# Oscillators.net
KiCad netlist of a schematic drawn in Altium Designer
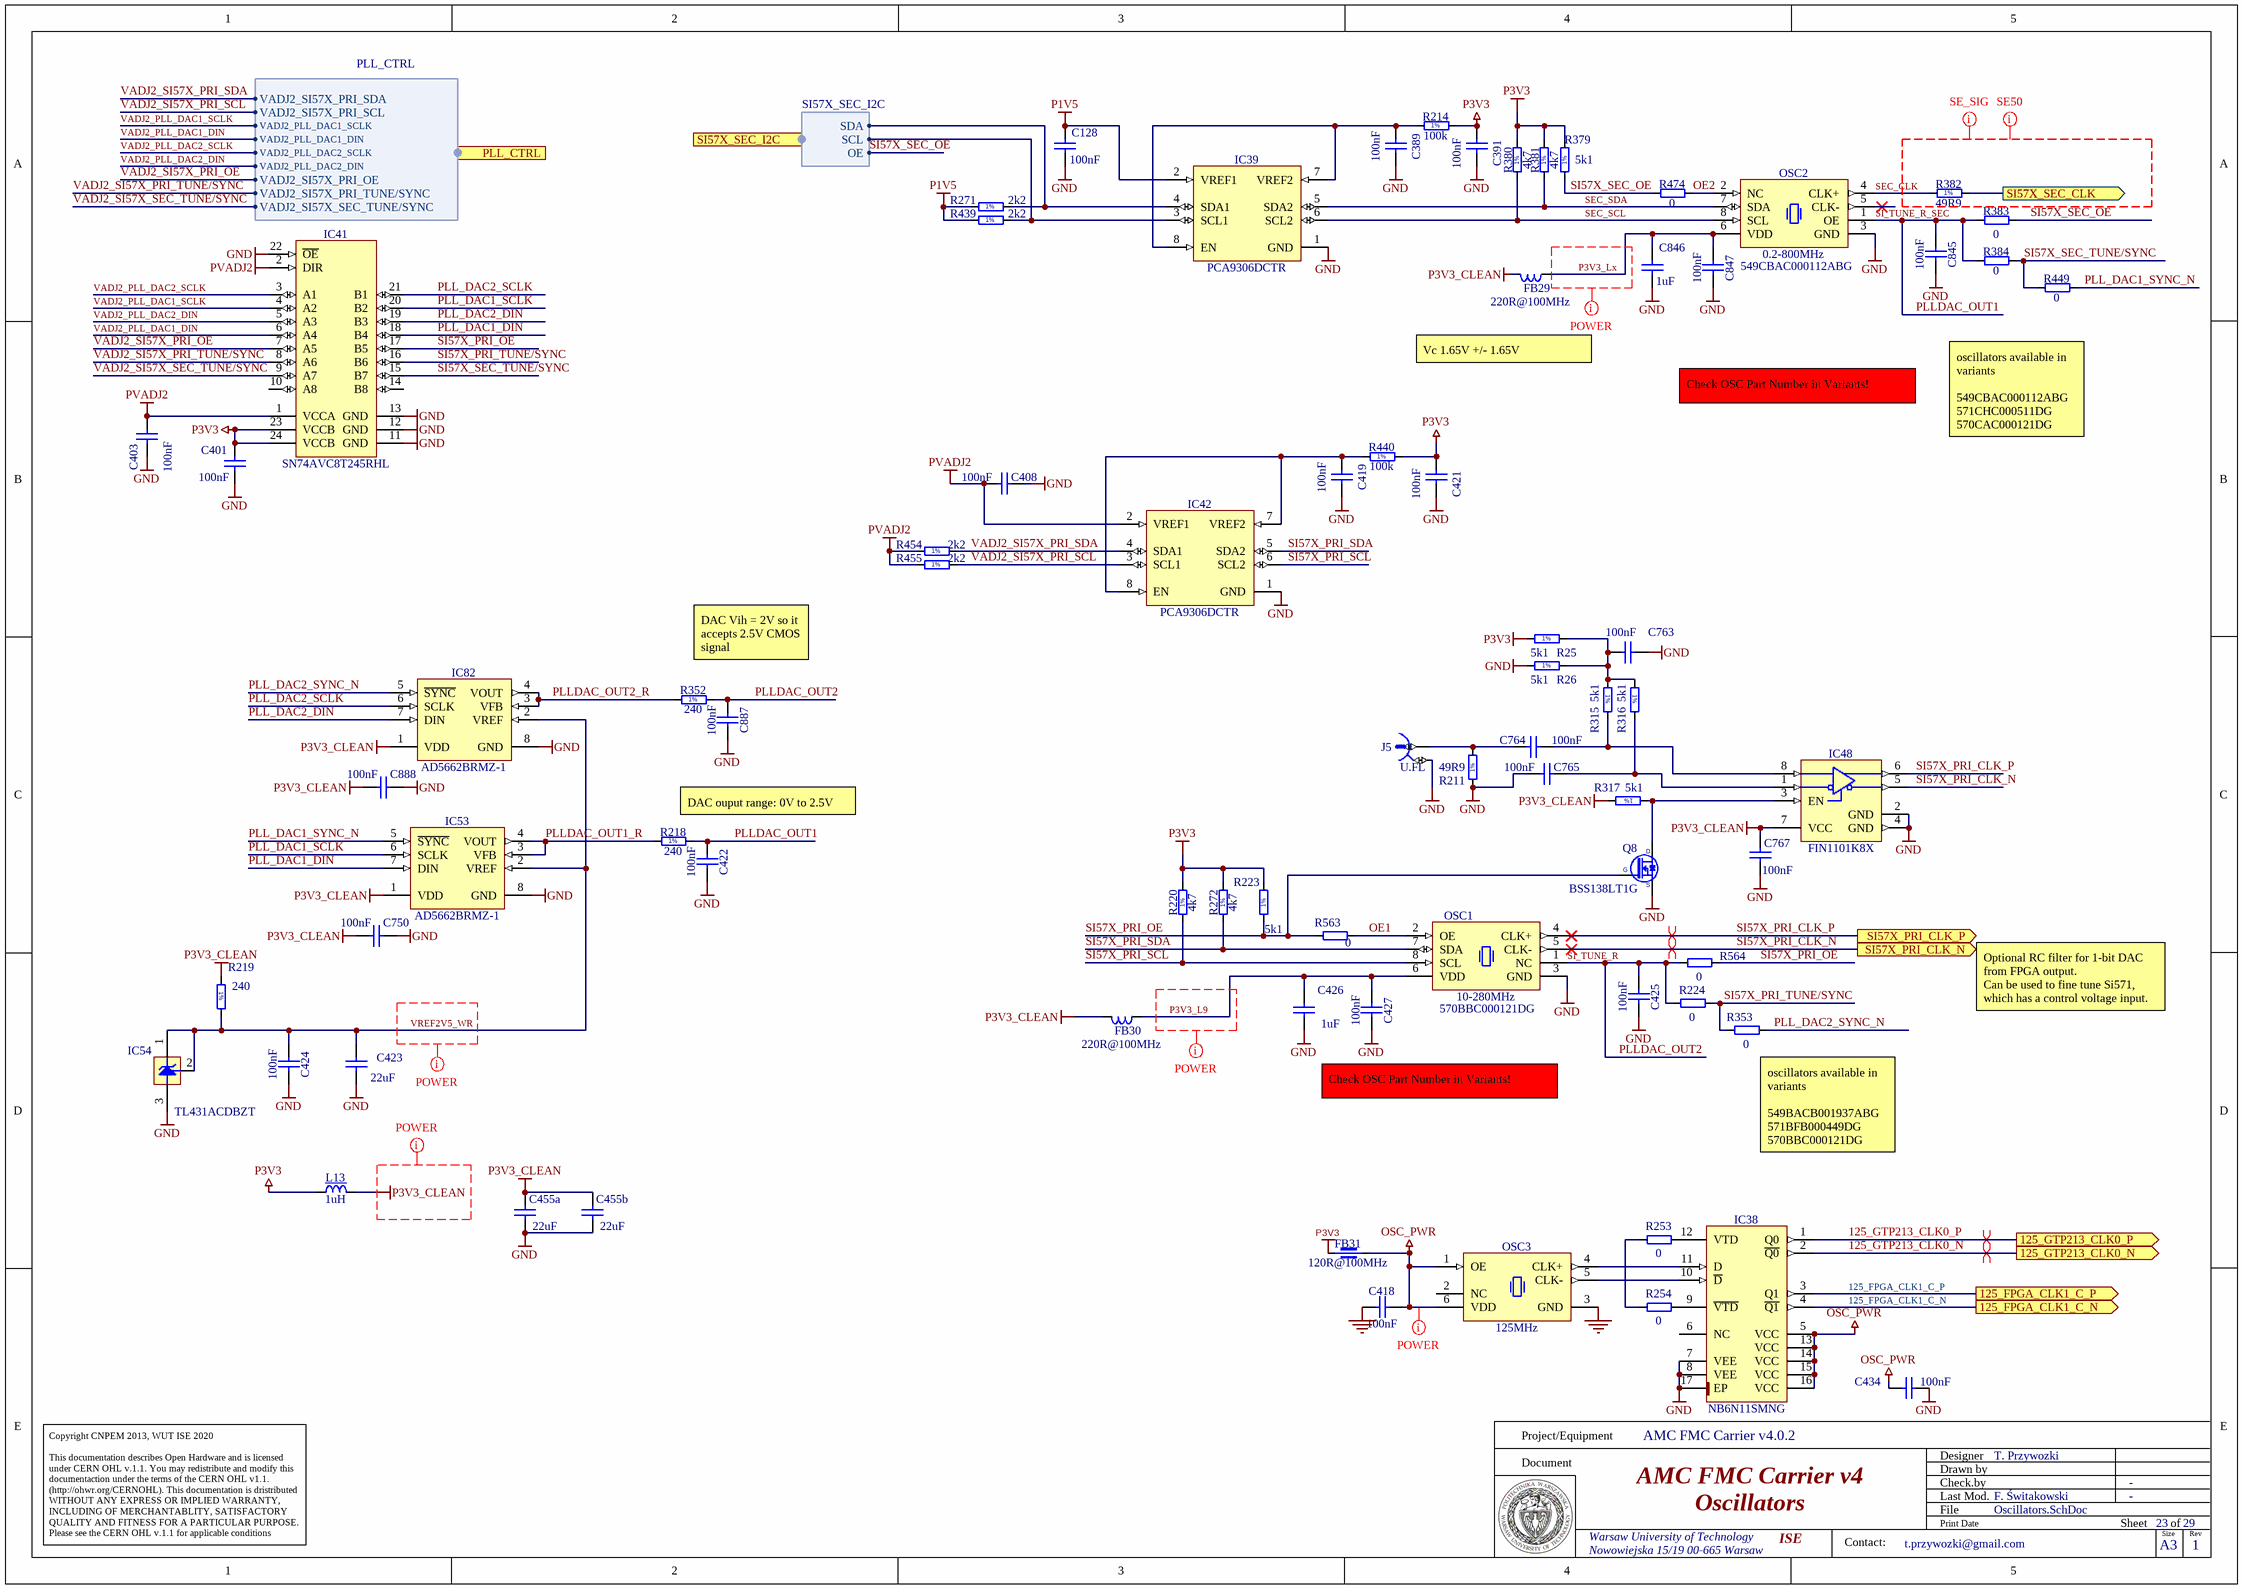
[diagram p0: Oscillators.SchDoc]

(export (version "E")
  (design (tool "Eeschema 10.0.6"))
  (components
    (comp (ref "C128")
      (value "100nF")
      (footprint "CAPC0603X33N")
      (description "Non-polarised capacitor")
      (fields
        (field (name "PART NUMBER") "CC0201_100NF_6.3V_10%_X5R")
        (field (name "VOLTAGE") "6.3V")
        (field (name "AUTHOR") "CERN DEM JLC")
      )
      (libsource (lib "Capacitors") (part "Capacitor - non polarized"))
    )
    (comp (ref "C389")
      (value "100nF")
      (footprint "CAPC0603X33N")
      (description "Non-polarised capacitor")
      (fields
        (field (name "PART NUMBER") "CC0201_100NF_6.3V_10%_X5R")
        (field (name "VOLTAGE") "6.3V")
        (field (name "AUTHOR") "CERN DEM JLC")
      )
      (libsource (lib "Capacitors") (part "Capacitor - non polarized"))
    )
    (comp (ref "C391")
      (value "100nF")
      (footprint "CAPC0603X33N")
      (description "Non-polarised capacitor")
      (fields
        (field (name "PART NUMBER") "CC0201_100NF_6.3V_10%_X5R")
        (field (name "VOLTAGE") "6.3V")
        (field (name "AUTHOR") "CERN DEM JLC")
      )
      (libsource (lib "Capacitors") (part "Capacitor - non polarized"))
    )
    (comp (ref "C401")
      (value "100nF")
      (footprint "CAPC0603X33N")
      (description "Non-polarised capacitor")
      (fields
        (field (name "PART NUMBER") "CC0201_100NF_6.3V_10%_X5R")
        (field (name "VOLTAGE") "6.3V")
        (field (name "AUTHOR") "CERN DEM JLC")
      )
      (libsource (lib "Capacitors") (part "Capacitor - non polarized"))
    )
    (comp (ref "C403")
      (value "100nF")
      (footprint "CAPC0603X33N")
      (description "Non-polarised capacitor")
      (fields
        (field (name "PART NUMBER") "CC0201_100NF_6.3V_10%_X5R")
        (field (name "VOLTAGE") "6.3V")
        (field (name "AUTHOR") "CERN DEM JLC")
      )
      (libsource (lib "Capacitors") (part "Capacitor - non polarized"))
    )
    (comp (ref "C408")
      (value "100nF")
      (footprint "CAPC0603X33N")
      (description "Non-polarised capacitor")
      (fields
        (field (name "PART NUMBER") "CC0201_100NF_6.3V_10%_X5R")
        (field (name "VOLTAGE") "6.3V")
        (field (name "AUTHOR") "CERN DEM JLC")
      )
      (libsource (lib "Capacitors") (part "Capacitor - non polarized"))
    )
    (comp (ref "C418")
      (value "100nF")
      (footprint "CAPC0603X33N")
      (description "Non-polarised capacitor")
      (fields
        (field (name "MANUFACTURER PART NUMBER") "CC0201_100NF_6.3V_10%_X5R")
        (field (name "MANUFACTURER") "GENERIC")
        (field (name "AUTHOR") "CERN DEM JLC")
      )
      (libsource (lib "Capacitors") (part "Capacitor - non polarized"))
    )
    (comp (ref "C419")
      (value "100nF")
      (footprint "CAPC0603X33N")
      (description "Non-polarised capacitor")
      (fields
        (field (name "PART NUMBER") "CC0201_100NF_6.3V_10%_X5R")
        (field (name "VOLTAGE") "6.3V")
        (field (name "AUTHOR") "CERN DEM JLC")
      )
      (libsource (lib "Capacitors") (part "Capacitor - non polarized"))
    )
    (comp (ref "C421")
      (value "100nF")
      (footprint "CAPC0603X33N")
      (description "Non-polarised capacitor")
      (fields
        (field (name "PART NUMBER") "CC0201_100NF_6.3V_10%_X5R")
        (field (name "VOLTAGE") "6.3V")
        (field (name "AUTHOR") "CERN DEM JLC")
      )
      (libsource (lib "Capacitors") (part "Capacitor - non polarized"))
    )
    (comp (ref "C422")
      (value "100nF")
      (footprint "CAPC0603X33N")
      (description "Non-polarised capacitor")
      (fields
        (field (name "PART NUMBER") "CC0201_100NF_6.3V_10%_X5R")
        (field (name "VOLTAGE") "6.3V")
        (field (name "AUTHOR") "CERN DEM JLC")
      )
      (libsource (lib "Capacitors") (part "Capacitor - non polarized"))
    )
    (comp (ref "C423")
      (value "22uF")
      (footprint "CAPC3216X180N")
      (description "Non-polarised capacitor")
      (fields
        (field (name "PART NUMBER") "CC1206_22UF_10V_10%_X7R")
        (field (name "VOLTAGE") "10V")
        (field (name "AUTHOR") "CERN DEM JLC")
      )
      (libsource (lib "Capacitors") (part "Capacitor - non polarized"))
    )
    (comp (ref "C424")
      (value "100nF")
      (footprint "CAPC0603X33N")
      (description "Non-polarised capacitor")
      (fields
        (field (name "PART NUMBER") "CC0201_100NF_6.3V_10%_X5R")
        (field (name "VOLTAGE") "6.3V")
        (field (name "AUTHOR") "CERN DEM JLC")
      )
      (libsource (lib "Capacitors") (part "Capacitor - non polarized"))
    )
    (comp (ref "C425")
      (value "100nF")
      (footprint "CAPC0603X33N")
      (description "Non-polarised capacitor")
      (fields
        (field (name "PART NUMBER") "CC0201_100NF_6.3V_10%_X5R")
        (field (name "VOLTAGE") "6.3V")
        (field (name "AUTHOR") "CERN DEM JLC")
      )
      (libsource (lib "Capacitors") (part "Capacitor - non polarized"))
    )
    (comp (ref "C426")
      (value "1uF")
      (footprint "CAPC1608X87N")
      (description "Non-polarised capacitor")
      (fields
        (field (name "PART NUMBER") "CC0603_1UF_16V_10%_X7R")
        (field (name "VOLTAGE") "16V")
        (field (name "AUTHOR") "CERN DEM JLC")
      )
      (libsource (lib "Capacitors") (part "Capacitor - non polarized"))
    )
    (comp (ref "C427")
      (value "100nF")
      (footprint "CAPC0603X33N")
      (description "Non-polarised capacitor")
      (fields
        (field (name "PART NUMBER") "CC0201_100NF_6.3V_10%_X5R")
        (field (name "VOLTAGE") "6.3V")
        (field (name "AUTHOR") "CERN DEM JLC")
      )
      (libsource (lib "Capacitors") (part "Capacitor - non polarized"))
    )
    (comp (ref "C434")
      (value "100nF")
      (footprint "CAPC0603X33N")
      (description "Non-polarised capacitor")
      (fields
        (field (name "PART NUMBER") "CC0201_100NF_6.3V_10%_X5R")
        (field (name "VOLTAGE") "6.3V")
        (field (name "AUTHOR") "CERN DEM JLC")
      )
      (libsource (lib "Capacitors") (part "Capacitor - non polarized"))
    )
    (comp (ref "C455a")
      (value "22uF")
      (footprint "CAPC3216X180N")
      (description "Non-polarised capacitor")
      (fields
        (field (name "PART NUMBER") "CC1206_22UF_10V_10%_X7R")
        (field (name "VOLTAGE") "10V")
        (field (name "AUTHOR") "CERN DEM JLC")
      )
      (libsource (lib "Capacitors") (part "Capacitor - non polarized"))
    )
    (comp (ref "C455b")
      (value "22uF")
      (footprint "CAPC3216X180N")
      (description "Non-polarised capacitor")
      (fields
        (field (name "PART NUMBER") "CC1206_22UF_10V_10%_X7R")
        (field (name "VOLTAGE") "10V")
        (field (name "AUTHOR") "CERN DEM JLC")
      )
      (libsource (lib "Capacitors") (part "Capacitor - non polarized"))
    )
    (comp (ref "C750")
      (value "100nF")
      (footprint "CAPC0603X33N")
      (description "Non-polarised capacitor")
      (fields
        (field (name "PART NUMBER") "CC0201_100NF_6.3V_10%_X5R")
        (field (name "VOLTAGE") "6.3V")
        (field (name "AUTHOR") "CERN DEM JLC")
      )
      (libsource (lib "Capacitors") (part "Capacitor - non polarized"))
    )
    (comp (ref "C763")
      (value "100nF")
      (footprint "CAPC0603X33N")
      (description "Non-polarised capacitor")
      (fields
        (field (name "PART NUMBER") "CC0201_100NF_6.3V_10%_X5R")
        (field (name "VOLTAGE") "6.3V")
        (field (name "AUTHOR") "CERN DEM JLC")
      )
      (libsource (lib "Capacitors") (part "Capacitor - non polarized"))
    )
    (comp (ref "C764")
      (value "100nF")
      (footprint "CAPC0603X33N")
      (description "Non-polarised capacitor")
      (fields
        (field (name "PART NUMBER") "CC0201_100NF_6.3V_10%_X5R")
        (field (name "VOLTAGE") "6.3V")
        (field (name "AUTHOR") "CERN DEM JLC")
      )
      (libsource (lib "Capacitors") (part "Capacitor - non polarized"))
    )
    (comp (ref "C765")
      (value "100nF")
      (footprint "CAPC0603X33N")
      (description "Non-polarised capacitor")
      (fields
        (field (name "PART NUMBER") "CC0201_100NF_6.3V_10%_X5R")
        (field (name "VOLTAGE") "6.3V")
        (field (name "AUTHOR") "CERN DEM JLC")
      )
      (libsource (lib "Capacitors") (part "Capacitor - non polarized"))
    )
    (comp (ref "C767")
      (value "100nF")
      (footprint "CAPC0603X33N")
      (description "Non-polarised capacitor")
      (fields
        (field (name "PART NUMBER") "CC0201_100NF_6.3V_10%_X5R")
        (field (name "VOLTAGE") "6.3V")
        (field (name "AUTHOR") "CERN DEM JLC")
      )
      (libsource (lib "Capacitors") (part "Capacitor - non polarized"))
    )
    (comp (ref "C845")
      (value "100nF")
      (footprint "CAPC0603X33N")
      (description "Non-polarised capacitor")
      (fields
        (field (name "PART NUMBER") "CC0201_100NF_6.3V_10%_X5R")
        (field (name "VOLTAGE") "6.3V")
        (field (name "AUTHOR") "CERN DEM JLC")
      )
      (libsource (lib "Capacitors") (part "Capacitor - non polarized"))
    )
    (comp (ref "C846")
      (value "1uF")
      (footprint "CAPC1608X87N")
      (description "Non-polarised capacitor")
      (fields
        (field (name "PART NUMBER") "CC0603_1UF_16V_10%_X7R")
        (field (name "VOLTAGE") "16V")
        (field (name "AUTHOR") "CERN DEM JLC")
      )
      (libsource (lib "Capacitors") (part "Capacitor - non polarized"))
    )
    (comp (ref "C847")
      (value "100nF")
      (footprint "CAPC0603X33N")
      (description "Non-polarised capacitor")
      (fields
        (field (name "PART NUMBER") "CC0201_100NF_6.3V_10%_X5R")
        (field (name "VOLTAGE") "6.3V")
        (field (name "AUTHOR") "CERN DEM JLC")
      )
      (libsource (lib "Capacitors") (part "Capacitor - non polarized"))
    )
    (comp (ref "C887")
      (value "100nF")
      (footprint "CAPC0603X33N")
      (description "Non-polarised capacitor")
      (fields
        (field (name "PART NUMBER") "CC0201_100NF_6.3V_10%_X5R")
        (field (name "VOLTAGE") "6.3V")
        (field (name "AUTHOR") "CERN DEM JLC")
      )
      (libsource (lib "Capacitors") (part "Capacitor - non polarized"))
    )
    (comp (ref "C888")
      (value "100nF")
      (footprint "CAPC0603X33N")
      (description "Non-polarised capacitor")
      (fields
        (field (name "PART NUMBER") "CC0201_100NF_6.3V_10%_X5R")
        (field (name "VOLTAGE") "6.3V")
        (field (name "AUTHOR") "CERN DEM JLC")
      )
      (libsource (lib "Capacitors") (part "Capacitor - non polarized"))
    )
    (comp (ref "FB29")
      (value "220R@100MHz")
      (footprint "INDC2012X105N")
      (description "Inductor")
      (fields
        (field (name "PART NUMBER") "IND0805_MURATA_BLM21PG221SN1D")
        (field (name "POWER") "2A")
        (field (name "AUTHOR") "CERN DEM JLC")
      )
      (libsource (lib "Inductors & Transformers") (part "Inductor"))
    )
    (comp (ref "FB30")
      (value "220R@100MHz")
      (footprint "INDC2012X105N")
      (description "Inductor")
      (fields
        (field (name "PART NUMBER") "IND0805_MURATA_BLM21PG221SN1D")
        (field (name "POWER") "2A")
        (field (name "AUTHOR") "CERN DEM JLC")
      )
      (libsource (lib "Inductors & Transformers") (part "Inductor"))
    )
    (comp (ref "FB31")
      (value "120R@100MHz")
      (footprint "INDC1005X55N")
      (fields
        (field (name "MANUFACTURER PART NUMBER") "BLM15PX121SN1D")
        (field (name "MANUFACTURER") "MURATA")
        (field (name "PART NUMBER") "IND0402_MURATA_BLM15PX121SN1D")
        (field (name "AUTHOR") "CERN DEM JMW")
      )
      (libsource (lib "Inductors & Transformers") (part "Ferrite Bead"))
    )
    (comp (ref "IC38")
      (value "NB6N11SMNG")
      (footprint "QFN50P300X300X100-17N-S185")
      (description "3.3V 1:2 AnyLevel Input to LVDS Fanout Buffer / Translator")
      (fields (field (name "MANUFACTURER") "ON SEMICONDUCTOR") (field (name "AUTHOR") "CERN DEM JLC"))
      (libsource (lib "ICs And Semiconductors") (part "NB6N11SMN"))
    )
    (comp (ref "IC39")
      (value "PCA9306DCTR")
      (footprint "SOP65P400X130-8N")
      (description "Dual Bidirectional I2C Bus And SMBus Voltage-Level Translator")
      (fields (field (name "MANUFACTURER") "TEXAS INSTRUMENTS") (field (name "AUTHOR") "CERN DEM JLC"))
      (libsource (lib "ICs And Semiconductors") (part "PCA9306D"))
    )
    (comp (ref "IC41")
      (value "SN74AVC8T245RHL")
      (footprint "TEXAS_RHL (S-PVQFN-N24)")
      (description "8-Bit Dual-Supply Bus Transceiver With Configurable Voltage Translation and 3-State Outputs")
      (fields (field (name "MANUFACTURER") "TEXAS INSTRUMENTS") (field (name "AUTHOR") "CERN DEM MR"))
      (libsource (lib "ICs And Semiconductors") (part "748T245"))
    )
    (comp (ref "IC42")
      (value "PCA9306DCTR")
      (footprint "SOP65P400X130-8N")
      (description "Dual Bidirectional I2C Bus And SMBus Voltage-Level Translator")
      (fields (field (name "MANUFACTURER") "TEXAS INSTRUMENTS") (field (name "AUTHOR") "CERN DEM JLC"))
      (libsource (lib "ICs And Semiconductors") (part "PCA9306D"))
    )
    (comp (ref "IC48")
      (value "FIN1101K8X")
      (footprint "SOP50P310X90-8N")
      (description "LVDS Single Port High Speed Repeater")
      (fields (field (name "MANUFACTURER") "FAIRCHILD SEMICONDUCTOR") (field (name "AUTHOR") "CERN DEM JLC"))
      (libsource (lib "ICs And Semiconductors") (part "FIN1101K8X"))
    )
    (comp (ref "IC53")
      (value "AD5662BRMZ-1")
      (footprint "SOP65P490X110-8N")
      (description "2.7V to 5.5V, 250uA, Rail-to-Rail Output 16-Bit nanoDAC")
      (fields (field (name "MANUFACTURER") "ANALOG DEVICES") (field (name "AUTHOR") "CERN DEM JLC"))
      (libsource (lib "ICs And Semiconductors") (part "AD5662"))
    )
    (comp (ref "IC54")
      (value "TL431ACDBZT")
      (footprint "SOT95P237X112-3N")
      (description "Precision Reference 1=Cathode 2=Adj 3=Anode")
      (fields (field (name "MANUFACTURER") "TEXAS INSTRUMENTS") (field (name "AUTHOR") "CERN DEM JLC"))
      (libsource (lib "ICs And Semiconductors") (part "VREF 1C-2ADJ-3A"))
    )
    (comp (ref "IC82")
      (value "AD5662BRMZ-1")
      (footprint "SOP65P490X110-8N")
      (description "2.7V to 5.5V, 250uA, Rail-to-Rail Output 16-Bit nanoDAC")
      (fields (field (name "MANUFACTURER") "ANALOG DEVICES") (field (name "AUTHOR") "CERN DEM JLC"))
      (libsource (lib "ICs And Semiconductors") (part "AD5662"))
    )
    (comp (ref "J5")
      (value "U.FL")
      (footprint "HIROSE_U.FL-R-SMT-1(10)")
      (fields
        (field (name "PART NUMBER") "HIROSE_U.FL-R-SMT-1(10)")
        (field (name "MANUFACTURER") "HIROSE (HRS)")
        (field (name "MANUFACTURER PART NUMBER") "U.FL-R-SMT-1(10)")
        (field (name "AUTHOR") "CERN DEM JLC")
      )
      (libsource (lib "Connectors") (part "Coax_1Male_1Shield"))
    )
    (comp (ref "L13")
      (value "1uH")
      (footprint "IND_PANASONIC_ELLVGG")
      (description "Inductor With Core")
      (fields
        (field (name "PART NUMBER") "IND_1UH_30%_PANASONIC_ELLVGG1R0N")
        (field (name "POWER") "1.8A")
        (field (name "AUTHOR") "CERN DEM JLC")
      )
      (libsource (lib "Inductors & Transformers") (part "Inductor With Magnetic core"))
    )
    (comp (ref "OSC1")
      (value "10-280MHz")
      (footprint "OSC_SILICON-LAB_SI570")
      (description "Any-Rate I2C Programmable XO Oscillator Si570 Serie")
      (fields
        (field (name "PART NUMBER") "OSC_10-280MHZ_SILICON-LAB_Si570BBC000121DG")
        (field (name "MANUFACTURER") "SILICON LABS")
        (field (name "MANUFACTURER PART NUMBER") "570BBC000121DG")
        (field (name "AUTHOR") "CERN DEM JLC")
      )
      (libsource (lib "ICs And Semiconductors") (part "Oscillator SILICON-LAB_Si570"))
    )
    (comp (ref "OSC2")
      (value "0.2-800MHz")
      (footprint "OSC_SILICON-LAB_SI549-A")
      (description "Ultra Low Jitter I2C Programmable Crystal Oscillator (XO), Si549 Series")
      (fields
        (field (name "PART NUMBER") "OSC_0.2-800MHZ_SILICON-LAB_549BACB001937ABG")
        (field (name "MANUFACTURER") "SILICON LABS")
        (field (name "MANUFACTURER PART NUMBER") "549CBAC000112ABG")
        (field (name "AUTHOR") "CERN DEM JMW")
      )
      (libsource (lib "ICs And Semiconductors") (part "Oscillator SILICON-LAB_Si549-CD"))
    )
    (comp (ref "OSC3")
      (value "125MHz")
      (footprint "OSC_SILICON-LAB_SI511-6N(3.2X5)")
      (description "Crystal Oscillator 6 pins, Si511 (LVDS/LVPECL/HCSL/Dual CMOS)")
      (fields
        (field (name "PART NUMBER") "OSC_125MHZ_SILICON-LAB_511BBA125M000BAGR")
        (field (name "MANUFACTURER") "SILICON LABS")
        (field (name "AUTHOR") "CERN DEM JLC")
      )
      (libsource (lib "ICs And Semiconductors") (part "Oscillator SILICON-LAB_Si511-6N"))
    )
    (comp (ref "Q8")
      (value "BSS138LT1G")
      (footprint "SOT95P240X110-3N")
      (description "N-CHANNEL MOSFET WITH DIODE")
      (fields (field (name "MANUFACTURER") "ON SEMICONDUCTOR") (field (name "AUTHOR") "CERN DEM JLC"))
      (libsource (lib "ICs And Semiconductors") (part "N-MOSFET-D 1G 2S 3D"))
    )
    (comp (ref "R25")
      (value "5k1")
      (footprint "RESC1608X55N")
      (description "Resistor - 1%")
      (fields
        (field (name "PART NUMBER") "R0603_5K1_1%_0.1W_100PPM")
        (field (name "POWER") "0.1W")
        (field (name "AUTHOR") "CERN DEM JLC")
      )
      (libsource (lib "Resistors") (part "Resistor - 1%"))
    )
    (comp (ref "R26")
      (value "5k1")
      (footprint "RESC1608X55N")
      (description "Resistor - 1%")
      (fields
        (field (name "PART NUMBER") "R0603_5K1_1%_0.1W_100PPM")
        (field (name "POWER") "0.1W")
        (field (name "AUTHOR") "CERN DEM JLC")
      )
      (libsource (lib "Resistors") (part "Resistor - 1%"))
    )
    (comp (ref "R211")
      (value "49R9")
      (footprint "RESC1005X40N")
      (description "Resistor - 1%")
      (fields
        (field (name "PART NUMBER") "R0402_49R9_1%_0.0625W_100PPM")
        (field (name "POWER") "0.0625W")
        (field (name "AUTHOR") "CERN DEM JLC")
      )
      (libsource (lib "Resistors") (part "Resistor - 1%"))
    )
    (comp (ref "R214")
      (value "100k")
      (footprint "RESC1005X40N")
      (description "Resistor - 1%")
      (fields
        (field (name "PART NUMBER") "R0402_100K_1%_0.0625W_100PPM")
        (field (name "POWER") "0.0625W")
        (field (name "AUTHOR") "CERN DEM JLC")
      )
      (libsource (lib "Resistors") (part "Resistor - 1%"))
    )
    (comp (ref "R218")
      (value "240")
      (footprint "RESC1005X40N")
      (description "Resistor - 1%")
      (fields
        (field (name "PART NUMBER") "R0402_240R_1%_0.0625W_100PPM")
        (field (name "POWER") "0.0625W")
        (field (name "AUTHOR") "CERN DEM JLC")
      )
      (libsource (lib "Resistors") (part "Resistor - 1%"))
    )
    (comp (ref "R219")
      (value "240")
      (footprint "RESC1005X40N")
      (description "Resistor - 1%")
      (fields
        (field (name "PART NUMBER") "R0402_240R_1%_0.0625W_100PPM")
        (field (name "POWER") "0.0625W")
        (field (name "AUTHOR") "CERN DEM JLC")
      )
      (libsource (lib "Resistors") (part "Resistor - 1%"))
    )
    (comp (ref "R220")
      (value "4k7")
      (footprint "RESC1005X40N")
      (description "Resistor - 1%")
      (fields
        (field (name "MANUFACTURER PART NUMBER") "R0402_4K7_1%_0.0625W_100PPM")
        (field (name "MANUFACTURER") "GENERIC")
        (field (name "AUTHOR") "CERN DEM JLC")
      )
      (libsource (lib "Resistors") (part "Resistor - 1%"))
    )
    (comp (ref "R223")
      (value "5k1")
      (footprint "RESC1608X55N")
      (description "Resistor - 1%")
      (fields
        (field (name "PART NUMBER") "R0603_5K1_1%_0.1W_100PPM")
        (field (name "POWER") "0.1W")
        (field (name "AUTHOR") "CERN DEM JLC")
      )
      (libsource (lib "Resistors") (part "Resistor - 1%"))
    )
    (comp (ref "R224")
      (value "0")
      (footprint "RESC1005X40N")
      (description "Resistor")
      (fields
        (field (name "PART NUMBER") "R0402_0R_JUMPER")
        (field (name "MANUFACTURER") "GENERIC")
        (field (name "AUTHOR") "CERN DEM JLC")
      )
      (libsource (lib "Resistors") (part "Resistor"))
    )
    (comp (ref "R253")
      (value "0")
      (footprint "RESC1005X40N")
      (description "Resistor")
      (fields
        (field (name "PART NUMBER") "R0402_0R_JUMPER")
        (field (name "MANUFACTURER") "GENERIC")
        (field (name "AUTHOR") "CERN DEM JLC")
      )
      (libsource (lib "Resistors") (part "Resistor"))
    )
    (comp (ref "R254")
      (value "0")
      (footprint "RESC1005X40N")
      (description "Resistor")
      (fields
        (field (name "PART NUMBER") "R0402_0R_JUMPER")
        (field (name "MANUFACTURER") "GENERIC")
        (field (name "AUTHOR") "CERN DEM JLC")
      )
      (libsource (lib "Resistors") (part "Resistor"))
    )
    (comp (ref "R271")
      (value "2k2")
      (footprint "RESC1005X40N")
      (description "Resistor - 1%")
      (fields
        (field (name "PART NUMBER") "R0402_2K2_1%_0.0625W_100PPM")
        (field (name "POWER") "0.0625W")
        (field (name "AUTHOR") "CERN DEM JLC")
      )
      (libsource (lib "Resistors") (part "Resistor - 1%"))
    )
    (comp (ref "R272")
      (value "4k7")
      (footprint "RESC1005X40N")
      (description "Resistor - 1%")
      (fields
        (field (name "MANUFACTURER PART NUMBER") "R0402_4K7_1%_0.0625W_100PPM")
        (field (name "MANUFACTURER") "GENERIC")
        (field (name "AUTHOR") "CERN DEM JLC")
      )
      (libsource (lib "Resistors") (part "Resistor - 1%"))
    )
    (comp (ref "R315")
      (value "5k1")
      (footprint "RESC1608X55N")
      (description "Resistor - 1%")
      (fields
        (field (name "PART NUMBER") "R0603_5K1_1%_0.1W_100PPM")
        (field (name "POWER") "0.1W")
        (field (name "AUTHOR") "CERN DEM JLC")
      )
      (libsource (lib "Resistors") (part "Resistor - 1%"))
    )
    (comp (ref "R316")
      (value "5k1")
      (footprint "RESC1608X55N")
      (description "Resistor - 1%")
      (fields
        (field (name "PART NUMBER") "R0603_5K1_1%_0.1W_100PPM")
        (field (name "POWER") "0.1W")
        (field (name "AUTHOR") "CERN DEM JLC")
      )
      (libsource (lib "Resistors") (part "Resistor - 1%"))
    )
    (comp (ref "R317")
      (value "5k1")
      (footprint "RESC1608X55N")
      (description "Resistor - 1%")
      (fields
        (field (name "PART NUMBER") "R0603_5K1_1%_0.1W_100PPM")
        (field (name "POWER") "0.1W")
        (field (name "AUTHOR") "CERN DEM JLC")
      )
      (libsource (lib "Resistors") (part "Resistor - 1%"))
    )
    (comp (ref "R352")
      (value "240")
      (footprint "RESC1005X40N")
      (description "Resistor - 1%")
      (fields
        (field (name "PART NUMBER") "R0402_240R_1%_0.0625W_100PPM")
        (field (name "POWER") "0.0625W")
        (field (name "AUTHOR") "CERN DEM JLC")
      )
      (libsource (lib "Resistors") (part "Resistor - 1%"))
    )
    (comp (ref "R353")
      (value "0")
      (footprint "RESC1005X40N")
      (description "Resistor")
      (fields
        (field (name "PART NUMBER") "R0402_0R_JUMPER")
        (field (name "MANUFACTURER") "GENERIC")
        (field (name "AUTHOR") "CERN DEM JLC")
      )
      (libsource (lib "Resistors") (part "Resistor"))
    )
    (comp (ref "R379")
      (value "5k1")
      (footprint "RESC1608X55N")
      (description "Resistor - 1%")
      (fields
        (field (name "PART NUMBER") "R0603_5K1_1%_0.1W_100PPM")
        (field (name "POWER") "0.1W")
        (field (name "AUTHOR") "CERN DEM JLC")
      )
      (libsource (lib "Resistors") (part "Resistor - 1%"))
    )
    (comp (ref "R380")
      (value "4k7")
      (footprint "RESC1005X40N")
      (description "Resistor - 1%")
      (fields
        (field (name "MANUFACTURER PART NUMBER") "R0402_4K7_1%_0.0625W_100PPM")
        (field (name "MANUFACTURER") "GENERIC")
        (field (name "AUTHOR") "CERN DEM JLC")
      )
      (libsource (lib "Resistors") (part "Resistor - 1%"))
    )
    (comp (ref "R381")
      (value "4k7")
      (footprint "RESC1005X40N")
      (description "Resistor - 1%")
      (fields
        (field (name "MANUFACTURER PART NUMBER") "R0402_4K7_1%_0.0625W_100PPM")
        (field (name "MANUFACTURER") "GENERIC")
        (field (name "AUTHOR") "CERN DEM JLC")
      )
      (libsource (lib "Resistors") (part "Resistor - 1%"))
    )
    (comp (ref "R382")
      (value "49R9")
      (footprint "RESC1005X40N")
      (description "Resistor - 1%")
      (fields
        (field (name "PART NUMBER") "R0402_49R9_1%_0.0625W_100PPM")
        (field (name "POWER") "0.0625W")
        (field (name "AUTHOR") "CERN DEM JLC")
      )
      (libsource (lib "Resistors") (part "Resistor - 1%"))
    )
    (comp (ref "R383")
      (value "0")
      (footprint "RESC1005X40N")
      (description "Resistor")
      (fields
        (field (name "PART NUMBER") "R0402_0R_JUMPER")
        (field (name "MANUFACTURER") "GENERIC")
        (field (name "AUTHOR") "CERN DEM JLC")
      )
      (libsource (lib "Resistors") (part "Resistor"))
    )
    (comp (ref "R384")
      (value "0")
      (footprint "RESC1005X40N")
      (description "Resistor")
      (fields
        (field (name "PART NUMBER") "R0402_0R_JUMPER")
        (field (name "MANUFACTURER") "GENERIC")
        (field (name "AUTHOR") "CERN DEM JLC")
      )
      (libsource (lib "Resistors") (part "Resistor"))
    )
    (comp (ref "R439")
      (value "2k2")
      (footprint "RESC1005X40N")
      (description "Resistor - 1%")
      (fields
        (field (name "PART NUMBER") "R0402_2K2_1%_0.0625W_100PPM")
        (field (name "POWER") "0.0625W")
        (field (name "AUTHOR") "CERN DEM JLC")
      )
      (libsource (lib "Resistors") (part "Resistor - 1%"))
    )
    (comp (ref "R440")
      (value "100k")
      (footprint "RESC1005X40N")
      (description "Resistor - 1%")
      (fields
        (field (name "PART NUMBER") "R0402_100K_1%_0.0625W_100PPM")
        (field (name "POWER") "0.0625W")
        (field (name "AUTHOR") "CERN DEM JLC")
      )
      (libsource (lib "Resistors") (part "Resistor - 1%"))
    )
    (comp (ref "R449")
      (value "0")
      (footprint "RESC1005X40N")
      (description "Resistor")
      (fields
        (field (name "PART NUMBER") "R0402_0R_JUMPER")
        (field (name "MANUFACTURER") "GENERIC")
        (field (name "AUTHOR") "CERN DEM JLC")
      )
      (libsource (lib "Resistors") (part "Resistor"))
    )
    (comp (ref "R454")
      (value "2k2")
      (footprint "RESC1005X40N")
      (description "Resistor - 1%")
      (fields
        (field (name "PART NUMBER") "R0402_2K2_1%_0.0625W_100PPM")
        (field (name "POWER") "0.0625W")
        (field (name "AUTHOR") "CERN DEM JLC")
      )
      (libsource (lib "Resistors") (part "Resistor - 1%"))
    )
    (comp (ref "R455")
      (value "2k2")
      (footprint "RESC1005X40N")
      (description "Resistor - 1%")
      (fields
        (field (name "PART NUMBER") "R0402_2K2_1%_0.0625W_100PPM")
        (field (name "POWER") "0.0625W")
        (field (name "AUTHOR") "CERN DEM JLC")
      )
      (libsource (lib "Resistors") (part "Resistor - 1%"))
    )
    (comp (ref "R474")
      (value "0")
      (footprint "RESC1005X40N")
      (description "Resistor")
      (fields
        (field (name "PART NUMBER") "R0402_0R_JUMPER")
        (field (name "MANUFACTURER") "GENERIC")
        (field (name "AUTHOR") "CERN DEM JLC")
      )
      (libsource (lib "Resistors") (part "Resistor"))
    )
    (comp (ref "R563")
      (value "0")
      (footprint "RESC1005X40N")
      (description "Resistor")
      (fields
        (field (name "PART NUMBER") "R0402_0R_JUMPER")
        (field (name "MANUFACTURER") "GENERIC")
        (field (name "AUTHOR") "CERN DEM JLC")
      )
      (libsource (lib "Resistors") (part "Resistor"))
    )
    (comp (ref "R564")
      (value "0")
      (footprint "RESC1005X40N")
      (description "Resistor")
      (fields
        (field (name "PART NUMBER") "R0402_0R_JUMPER")
        (field (name "MANUFACTURER") "GENERIC")
        (field (name "AUTHOR") "CERN DEM JLC")
      )
      (libsource (lib "Resistors") (part "Resistor"))
    )
  )
  (nets
    (net (code "3") (name "/125_FPGA_CLK1_C_N") (class "Default")
      (node (ref "IC38") (pin "4") (pinfunction "~{Q1}_4") (pintype "output"))
    )
    (net (code "4") (name "/125_FPGA_CLK1_C_P") (class "Default")
      (node (ref "IC38") (pin "3") (pinfunction "Q1_3") (pintype "output"))
    )
    (net (code "5") (name "/125_GTP213_CLK0_N") (class "Default")
      (node (ref "IC38") (pin "2") (pinfunction "~{Q0}_2") (pintype "output"))
    )
    (net (code "6") (name "/125_GTP213_CLK0_P") (class "Default")
      (node (ref "IC38") (pin "1") (pinfunction "Q0_1") (pintype "output"))
    )
    (net (code "7") (name "/OE1") (class "Default")
      (node (ref "OSC1") (pin "2") (pinfunction "OE_2") (pintype "input"))
      (node (ref "R563") (pin "2") (pinfunction "2_2") (pintype "passive"))
    )
    (net (code "8") (name "/OE2") (class "Default")
      (node (ref "OSC2") (pin "2") (pinfunction "NC_2") (pintype "input"))
      (node (ref "R474") (pin "2") (pinfunction "2_2") (pintype "passive"))
    )
    (net (code "9") (name "/P3V3_L9") (class "Default")
      (node (ref "C426") (pin "2") (pinfunction "2_2") (pintype "passive"))
      (node (ref "C427") (pin "1") (pinfunction "1_1") (pintype "passive"))
      (node (ref "FB30") (pin "1") (pinfunction "1_1") (pintype "passive"))
      (node (ref "OSC1") (pin "6") (pinfunction "VDD_6") (pintype "power_in"))
    )
    (net (code "10") (name "/P3V3_Lx") (class "Default")
      (node (ref "C846") (pin "2") (pinfunction "2_2") (pintype "passive"))
      (node (ref "C847") (pin "1") (pinfunction "1_1") (pintype "passive"))
      (node (ref "FB29") (pin "1") (pinfunction "1_1") (pintype "passive"))
      (node (ref "OSC2") (pin "6") (pinfunction "VDD_6") (pintype "power_in"))
    )
    (net (code "11") (name "/PLLDAC_OUT1") (class "Default")
      (node (ref "C422") (pin "1") (pinfunction "1_1") (pintype "passive"))
      (node (ref "C845") (pin "1") (pinfunction "1_1") (pintype "passive"))
      (node (ref "OSC2") (pin "1") (pinfunction "OE_1") (pintype "passive"))
      (node (ref "R218") (pin "2") (pinfunction "2_2") (pintype "passive"))
      (node (ref "R383") (pin "1") (pinfunction "1_1") (pintype "passive"))
      (node (ref "R384") (pin "2") (pinfunction "2_2") (pintype "passive"))
    )
    (net (code "12") (name "/PLLDAC_OUT1_R") (class "Default")
      (node (ref "IC53") (pin "3") (pinfunction "VFB_3") (pintype "input"))
      (node (ref "IC53") (pin "4") (pinfunction "VOUT_4") (pintype "output"))
      (node (ref "R218") (pin "1") (pinfunction "1_1") (pintype "passive"))
    )
    (net (code "13") (name "/PLLDAC_OUT2") (class "Default")
      (node (ref "C425") (pin "1") (pinfunction "1_1") (pintype "passive"))
      (node (ref "C887") (pin "1") (pinfunction "1_1") (pintype "passive"))
      (node (ref "OSC1") (pin "1") (pinfunction "NC_1") (pintype "passive"))
      (node (ref "R224") (pin "1") (pinfunction "1_1") (pintype "passive"))
      (node (ref "R352") (pin "2") (pinfunction "2_2") (pintype "passive"))
      (node (ref "R564") (pin "1") (pinfunction "1_1") (pintype "passive"))
    )
    (net (code "14") (name "/PLLDAC_OUT2_R") (class "Default")
      (node (ref "IC82") (pin "3") (pinfunction "VFB_3") (pintype "input"))
      (node (ref "IC82") (pin "4") (pinfunction "VOUT_4") (pintype "output"))
      (node (ref "R352") (pin "1") (pinfunction "1_1") (pintype "passive"))
    )
    (net (code "15") (name "/PLL_DAC1_DIN") (class "Default")
      (node (ref "IC41") (pin "18") (pinfunction "B4_18") (pintype "bidirectional"))
      (node (ref "IC53") (pin "7") (pinfunction "DIN_7") (pintype "input"))
    )
    (net (code "16") (name "/PLL_DAC1_SCLK") (class "Default")
      (node (ref "IC41") (pin "20") (pinfunction "B2_20") (pintype "bidirectional"))
      (node (ref "IC53") (pin "6") (pinfunction "SCLK_6") (pintype "input"))
    )
    (net (code "17") (name "/PLL_DAC1_SYNC_N") (class "Default")
      (node (ref "IC53") (pin "5") (pinfunction "~{SYNC}_5") (pintype "input"))
      (node (ref "R449") (pin "1") (pinfunction "1_1") (pintype "passive"))
    )
    (net (code "18") (name "/PLL_DAC2_DIN") (class "Default")
      (node (ref "IC41") (pin "19") (pinfunction "B3_19") (pintype "bidirectional"))
      (node (ref "IC82") (pin "7") (pinfunction "DIN_7") (pintype "input"))
    )
    (net (code "19") (name "/PLL_DAC2_SCLK") (class "Default")
      (node (ref "IC41") (pin "21") (pinfunction "B1_21") (pintype "bidirectional"))
      (node (ref "IC82") (pin "6") (pinfunction "SCLK_6") (pintype "input"))
    )
    (net (code "20") (name "/PLL_DAC2_SYNC_N") (class "Default")
      (node (ref "IC82") (pin "5") (pinfunction "~{SYNC}_5") (pintype "input"))
      (node (ref "R353") (pin "1") (pinfunction "1_1") (pintype "passive"))
    )
    (net (code "21") (name "/SEC_CLK") (class "Default")
      (node (ref "OSC2") (pin "4") (pinfunction "CLK+_4") (pintype "output"))
      (node (ref "R382") (pin "1") (pinfunction "1_1") (pintype "passive"))
    )
    (net (code "22") (name "/SEC_SCL") (class "Default")
      (node (ref "IC39") (pin "6") (pinfunction "SCL2_6") (pintype "bidirectional"))
      (node (ref "OSC2") (pin "8") (pinfunction "SCL_8") (pintype "input"))
      (node (ref "R380") (pin "1") (pinfunction "1_1") (pintype "passive"))
    )
    (net (code "23") (name "/SEC_SDA") (class "Default")
      (node (ref "IC39") (pin "5") (pinfunction "SDA2_5") (pintype "bidirectional"))
      (node (ref "OSC2") (pin "7") (pinfunction "SDA_7") (pintype "bidirectional"))
      (node (ref "R381") (pin "1") (pinfunction "1_1") (pintype "passive"))
    )
    (net (code "24") (name "/SI57X_PRI_CLK_N") (class "Default")
      (node (ref "IC48") (pin "5") (pinfunction "DOUT-_5") (pintype "output"))
      (node (ref "OSC1") (pin "5") (pinfunction "CLK-_5") (pintype "output"))
    )
    (net (code "25") (name "/SI57X_PRI_CLK_P") (class "Default")
      (node (ref "IC48") (pin "6") (pinfunction "DOUT+_6") (pintype "output"))
      (node (ref "OSC1") (pin "4") (pinfunction "CLK+_4") (pintype "output"))
    )
    (net (code "26") (name "/SI57X_PRI_OE") (class "Default")
      (node (ref "IC41") (pin "17") (pinfunction "B5_17") (pintype "bidirectional"))
      (node (ref "Q8") (pin "1") (pinfunction "G_1") (pintype "passive"))
      (node (ref "R223") (pin "1") (pinfunction "1_1") (pintype "passive"))
      (node (ref "R563") (pin "1") (pinfunction "1_1") (pintype "passive"))
      (node (ref "R564") (pin "2") (pinfunction "2_2") (pintype "passive"))
    )
    (net (code "27") (name "/SI57X_PRI_SCL") (class "Default")
      (node (ref "IC42") (pin "6") (pinfunction "SCL2_6") (pintype "bidirectional"))
      (node (ref "OSC1") (pin "8") (pinfunction "SCL_8") (pintype "input"))
      (node (ref "R220") (pin "1") (pinfunction "1_1") (pintype "passive"))
    )
    (net (code "28") (name "/SI57X_PRI_SDA") (class "Default")
      (node (ref "IC42") (pin "5") (pinfunction "SDA2_5") (pintype "bidirectional"))
      (node (ref "OSC1") (pin "7") (pinfunction "SDA_7") (pintype "bidirectional"))
      (node (ref "R272") (pin "1") (pinfunction "1_1") (pintype "passive"))
    )
    (net (code "29") (name "/SI57X_PRI_TUNE{slash}SYNC") (class "Default")
      (node (ref "IC41") (pin "16") (pinfunction "B6_16") (pintype "bidirectional"))
      (node (ref "R224") (pin "2") (pinfunction "2_2") (pintype "passive"))
      (node (ref "R353") (pin "2") (pinfunction "2_2") (pintype "passive"))
    )
    (net (code "30") (name "/SI57X_SEC_CLK") (class "Default")
      (node (ref "R382") (pin "2") (pinfunction "2_2") (pintype "passive"))
    )
    (net (code "31") (name "/SI57X_SEC_OE") (class "Default")
      (node (ref "R379") (pin "1") (pinfunction "1_1") (pintype "passive"))
      (node (ref "R383") (pin "2") (pinfunction "2_2") (pintype "passive"))
      (node (ref "R474") (pin "1") (pinfunction "1_1") (pintype "passive"))
    )
    (net (code "32") (name "/SI57X_SEC_TUNE{slash}SYNC") (class "Default")
      (node (ref "IC41") (pin "15") (pinfunction "B7_15") (pintype "bidirectional"))
      (node (ref "R384") (pin "1") (pinfunction "1_1") (pintype "passive"))
      (node (ref "R449") (pin "2") (pinfunction "2_2") (pintype "passive"))
    )
    (net (code "33") (name "/VADJ2_PLL_DAC1_DIN") (class "Default")
      (node (ref "IC41") (pin "6") (pinfunction "A4_6") (pintype "bidirectional"))
    )
    (net (code "34") (name "/VADJ2_PLL_DAC1_SCLK") (class "Default")
      (node (ref "IC41") (pin "4") (pinfunction "A2_4") (pintype "bidirectional"))
    )
    (net (code "35") (name "/VADJ2_PLL_DAC2_DIN") (class "Default")
      (node (ref "IC41") (pin "5") (pinfunction "A3_5") (pintype "bidirectional"))
    )
    (net (code "36") (name "/VADJ2_PLL_DAC2_SCLK") (class "Default")
      (node (ref "IC41") (pin "3") (pinfunction "A1_3") (pintype "bidirectional"))
    )
    (net (code "37") (name "/VADJ2_SI57X_PRI_OE") (class "Default")
      (node (ref "IC41") (pin "7") (pinfunction "A5_7") (pintype "bidirectional"))
    )
    (net (code "38") (name "/VADJ2_SI57X_PRI_SCL") (class "Default")
      (node (ref "IC42") (pin "3") (pinfunction "SCL1_3") (pintype "bidirectional"))
      (node (ref "R455") (pin "2") (pinfunction "2_2") (pintype "passive"))
    )
    (net (code "39") (name "/VADJ2_SI57X_PRI_SDA") (class "Default")
      (node (ref "IC42") (pin "4") (pinfunction "SDA1_4") (pintype "bidirectional"))
      (node (ref "R454") (pin "2") (pinfunction "2_2") (pintype "passive"))
    )
    (net (code "40") (name "/VADJ2_SI57X_PRI_TUNE{slash}SYNC") (class "Default")
      (node (ref "IC41") (pin "8") (pinfunction "A6_8") (pintype "bidirectional"))
    )
    (net (code "41") (name "/VADJ2_SI57X_SEC_TUNE{slash}SYNC") (class "Default")
      (node (ref "IC41") (pin "9") (pinfunction "A7_9") (pintype "bidirectional"))
    )
    (net (code "42") (name "/VREF2V5_WR") (class "Default")
      (node (ref "C423") (pin "2") (pinfunction "2_2") (pintype "passive"))
      (node (ref "C424") (pin "1") (pinfunction "1_1") (pintype "passive"))
      (node (ref "IC53") (pin "2") (pinfunction "VREF_2") (pintype "input"))
      (node (ref "IC54") (pin "1") (pinfunction "C_1") (pintype "passive"))
      (node (ref "IC54") (pin "2") (pinfunction "Adj_2") (pintype "passive"))
      (node (ref "IC82") (pin "2") (pinfunction "VREF_2") (pintype "input"))
      (node (ref "R219") (pin "2") (pinfunction "2_2") (pintype "passive"))
    )
    (net (code "45") (name "GND") (class "Default")
      (node (ref "C128") (pin "1") (pinfunction "1_1") (pintype "passive"))
      (node (ref "C389") (pin "1") (pinfunction "1_1") (pintype "passive"))
      (node (ref "C391") (pin "1") (pinfunction "1_1") (pintype "passive"))
      (node (ref "C401") (pin "1") (pinfunction "1_1") (pintype "passive"))
      (node (ref "C403") (pin "1") (pinfunction "1_1") (pintype "passive"))
      (node (ref "C408") (pin "1") (pinfunction "1_1") (pintype "passive"))
      (node (ref "C418") (pin "1") (pinfunction "1_1") (pintype "passive"))
      (node (ref "C419") (pin "1") (pinfunction "1_1") (pintype "passive"))
      (node (ref "C421") (pin "1") (pinfunction "1_1") (pintype "passive"))
      (node (ref "C422") (pin "2") (pinfunction "2_2") (pintype "passive"))
      (node (ref "C423") (pin "1") (pinfunction "1_1") (pintype "passive"))
      (node (ref "C424") (pin "2") (pinfunction "2_2") (pintype "passive"))
      (node (ref "C425") (pin "2") (pinfunction "2_2") (pintype "passive"))
      (node (ref "C426") (pin "1") (pinfunction "1_1") (pintype "passive"))
      (node (ref "C427") (pin "2") (pinfunction "2_2") (pintype "passive"))
      (node (ref "C434") (pin "1") (pinfunction "1_1") (pintype "passive"))
      (node (ref "C455a") (pin "1") (pinfunction "1_1") (pintype "passive"))
      (node (ref "C455b") (pin "1") (pinfunction "1_1") (pintype "passive"))
      (node (ref "C750") (pin "2") (pinfunction "2_2") (pintype "passive"))
      (node (ref "C763") (pin "2") (pinfunction "2_2") (pintype "passive"))
      (node (ref "C765") (pin "1") (pinfunction "1_1") (pintype "passive"))
      (node (ref "C767") (pin "2") (pinfunction "2_2") (pintype "passive"))
      (node (ref "C845") (pin "2") (pinfunction "2_2") (pintype "passive"))
      (node (ref "C846") (pin "1") (pinfunction "1_1") (pintype "passive"))
      (node (ref "C847") (pin "2") (pinfunction "2_2") (pintype "passive"))
      (node (ref "C887") (pin "2") (pinfunction "2_2") (pintype "passive"))
      (node (ref "C888") (pin "2") (pinfunction "2_2") (pintype "passive"))
      (node (ref "IC38") (pin "17") (pinfunction "EP_17") (pintype "power_in"))
      (node (ref "IC38") (pin "7") (pinfunction "VEE_7") (pintype "power_in"))
      (node (ref "IC38") (pin "8") (pinfunction "VEE_8") (pintype "power_in"))
      (node (ref "IC39") (pin "1") (pinfunction "GND_1") (pintype "power_in"))
      (node (ref "IC41") (pin "11") (pinfunction "GND_11") (pintype "power_in"))
      (node (ref "IC41") (pin "12") (pinfunction "GND_12") (pintype "power_in"))
      (node (ref "IC41") (pin "13") (pinfunction "GND_13") (pintype "power_in"))
      (node (ref "IC41") (pin "22") (pinfunction "~{OE}_22") (pintype "input"))
      (node (ref "IC42") (pin "1") (pinfunction "GND_1") (pintype "power_in"))
      (node (ref "IC48") (pin "2") (pinfunction "GND_2") (pintype "power_in"))
      (node (ref "IC48") (pin "4") (pinfunction "GND_4") (pintype "output"))
      (node (ref "IC53") (pin "8") (pinfunction "GND_8") (pintype "power_in"))
      (node (ref "IC54") (pin "3") (pinfunction "A_3") (pintype "passive"))
      (node (ref "IC82") (pin "8") (pinfunction "GND_8") (pintype "power_in"))
      (node (ref "J5") (pin "2") (pinfunction "2_2") (pintype "bidirectional"))
      (node (ref "OSC1") (pin "3") (pinfunction "GND_3") (pintype "power_in"))
      (node (ref "OSC2") (pin "3") (pinfunction "GND_3") (pintype "power_in"))
      (node (ref "OSC3") (pin "3") (pinfunction "GND_3") (pintype "power_in"))
      (node (ref "Q8") (pin "2") (pinfunction "S_2") (pintype "passive"))
      (node (ref "R211") (pin "1") (pinfunction "1_1") (pintype "passive"))
      (node (ref "R26") (pin "1") (pinfunction "1_1") (pintype "passive"))
    )
    (net (code "46") (name "Net-(C763-Pad1)") (class "Default")
      (node (ref "C763") (pin "1") (pinfunction "1_1") (pintype "passive"))
      (node (ref "R25") (pin "2") (pinfunction "2_2") (pintype "passive"))
      (node (ref "R26") (pin "2") (pinfunction "2_2") (pintype "passive"))
      (node (ref "R315") (pin "1") (pinfunction "1_1") (pintype "passive"))
      (node (ref "R316") (pin "1") (pinfunction "1_1") (pintype "passive"))
    )
    (net (code "47") (name "Net-(C764-Pad2)") (class "Default")
      (node (ref "C764") (pin "2") (pinfunction "2_2") (pintype "passive"))
      (node (ref "J5") (pin "1") (pinfunction "1_1") (pintype "bidirectional"))
      (node (ref "R211") (pin "2") (pinfunction "2_2") (pintype "passive"))
    )
    (net (code "48") (name "Net-(IC38-D)") (class "Default")
      (node (ref "IC38") (pin "11") (pinfunction "D_11") (pintype "input"))
      (node (ref "OSC3") (pin "4") (pinfunction "CLK+_4") (pintype "output"))
    )
    (net (code "49") (name "Net-(IC38-VTD)") (class "Default")
      (node (ref "IC38") (pin "12") (pinfunction "VTD_12") (pintype "passive"))
      (node (ref "R253") (pin "2") (pinfunction "2_2") (pintype "passive"))
    )
    (net (code "50") (name "Net-(IC38-~{D})") (class "Default")
      (node (ref "IC38") (pin "10") (pinfunction "~{D}_10") (pintype "input"))
      (node (ref "OSC3") (pin "5") (pinfunction "CLK-_5") (pintype "output"))
    )
    (net (code "51") (name "Net-(IC38-~{VTD})") (class "Default")
      (node (ref "IC38") (pin "9") (pinfunction "~{VTD}_9") (pintype "passive"))
      (node (ref "R254") (pin "2") (pinfunction "2_2") (pintype "passive"))
    )
    (net (code "52") (name "Net-(IC39-EN)") (class "Default")
      (node (ref "C389") (pin "2") (pinfunction "2_2") (pintype "passive"))
      (node (ref "IC39") (pin "7") (pinfunction "VREF2_7") (pintype "input"))
      (node (ref "IC39") (pin "8") (pinfunction "EN_8") (pintype "input"))
      (node (ref "R214") (pin "1") (pinfunction "1_1") (pintype "passive"))
    )
    (net (code "53") (name "Net-(IC39-SCL1)") (class "Default")
      (node (ref "IC39") (pin "3") (pinfunction "SCL1_3") (pintype "bidirectional"))
      (node (ref "R439") (pin "2") (pinfunction "2_2") (pintype "passive"))
    )
    (net (code "54") (name "Net-(IC39-SDA1)") (class "Default")
      (node (ref "IC39") (pin "4") (pinfunction "SDA1_4") (pintype "bidirectional"))
      (node (ref "R271") (pin "2") (pinfunction "2_2") (pintype "passive"))
    )
    (net (code "55") (name "Net-(IC42-EN)") (class "Default")
      (node (ref "C419") (pin "2") (pinfunction "2_2") (pintype "passive"))
      (node (ref "IC42") (pin "7") (pinfunction "VREF2_7") (pintype "input"))
      (node (ref "IC42") (pin "8") (pinfunction "EN_8") (pintype "input"))
      (node (ref "R440") (pin "1") (pinfunction "1_1") (pintype "passive"))
    )
    (net (code "56") (name "Net-(IC48-EN)") (class "Default")
      (node (ref "IC48") (pin "3") (pinfunction "EN_3") (pintype "input"))
      (node (ref "Q8") (pin "3") (pinfunction "D_3") (pintype "passive"))
      (node (ref "R317") (pin "1") (pinfunction "1_1") (pintype "passive"))
    )
    (net (code "57") (name "Net-(IC48-RIN+)") (class "Default")
      (node (ref "C764") (pin "1") (pinfunction "1_1") (pintype "passive"))
      (node (ref "IC48") (pin "8") (pinfunction "RIN+_8") (pintype "input"))
      (node (ref "R315") (pin "2") (pinfunction "2_2") (pintype "passive"))
    )
    (net (code "58") (name "Net-(IC48-RIN-)") (class "Default")
      (node (ref "C765") (pin "2") (pinfunction "2_2") (pintype "passive"))
      (node (ref "IC48") (pin "1") (pinfunction "RIN-_1") (pintype "input"))
      (node (ref "R316") (pin "2") (pinfunction "2_2") (pintype "passive"))
    )
    (net (code "59") (name "Net-(R253-Pad1)") (class "Default")
      (node (ref "R253") (pin "1") (pinfunction "1_1") (pintype "passive"))
      (node (ref "R254") (pin "1") (pinfunction "1_1") (pintype "passive"))
    )
    (net (code "60") (name "OSC_PWR") (class "Default")
      (node (ref "C418") (pin "2") (pinfunction "2_2") (pintype "passive"))
      (node (ref "C434") (pin "2") (pinfunction "2_2") (pintype "passive"))
      (node (ref "FB31") (pin "1") (pinfunction "1_1") (pintype "passive"))
      (node (ref "IC38") (pin "13") (pinfunction "VCC_13") (pintype "power_in"))
      (node (ref "IC38") (pin "14") (pinfunction "VCC_14") (pintype "power_in"))
      (node (ref "IC38") (pin "15") (pinfunction "VCC_15") (pintype "power_in"))
      (node (ref "IC38") (pin "16") (pinfunction "VCC_16") (pintype "power_in"))
      (node (ref "IC38") (pin "5") (pinfunction "VCC_5") (pintype "power_in"))
      (node (ref "OSC3") (pin "1") (pinfunction "OE_1") (pintype "input"))
      (node (ref "OSC3") (pin "6") (pinfunction "VDD_6") (pintype "power_in"))
    )
    (net (code "61") (name "P1V5") (class "Default")
      (node (ref "C128") (pin "2") (pinfunction "2_2") (pintype "passive"))
      (node (ref "IC39") (pin "2") (pinfunction "VREF1_2") (pintype "input"))
      (node (ref "R271") (pin "1") (pinfunction "1_1") (pintype "passive"))
      (node (ref "R439") (pin "1") (pinfunction "1_1") (pintype "passive"))
    )
    (net (code "62") (name "P3V3") (class "Default")
      (node (ref "C391") (pin "2") (pinfunction "2_2") (pintype "passive"))
      (node (ref "C401") (pin "2") (pinfunction "2_2") (pintype "passive"))
      (node (ref "C421") (pin "2") (pinfunction "2_2") (pintype "passive"))
      (node (ref "FB31") (pin "2") (pinfunction "2_2") (pintype "passive"))
      (node (ref "IC41") (pin "23") (pinfunction "VCCB_23") (pintype "power_in"))
      (node (ref "IC41") (pin "24") (pinfunction "VCCB_24") (pintype "power_in"))
      (node (ref "L13") (pin "1") (pinfunction "1_1") (pintype "passive"))
      (node (ref "R214") (pin "2") (pinfunction "2_2") (pintype "passive"))
      (node (ref "R220") (pin "2") (pinfunction "2_2") (pintype "passive"))
      (node (ref "R223") (pin "2") (pinfunction "2_2") (pintype "passive"))
      (node (ref "R25") (pin "1") (pinfunction "1_1") (pintype "passive"))
      (node (ref "R272") (pin "2") (pinfunction "2_2") (pintype "passive"))
      (node (ref "R379") (pin "2") (pinfunction "2_2") (pintype "passive"))
      (node (ref "R380") (pin "2") (pinfunction "2_2") (pintype "passive"))
      (node (ref "R381") (pin "2") (pinfunction "2_2") (pintype "passive"))
      (node (ref "R440") (pin "2") (pinfunction "2_2") (pintype "passive"))
    )
    (net (code "63") (name "P3V3_CLEAN") (class "Default")
      (node (ref "C455a") (pin "2") (pinfunction "2_2") (pintype "passive"))
      (node (ref "C455b") (pin "2") (pinfunction "2_2") (pintype "passive"))
      (node (ref "C750") (pin "1") (pinfunction "1_1") (pintype "passive"))
      (node (ref "C767") (pin "1") (pinfunction "1_1") (pintype "passive"))
      (node (ref "C888") (pin "1") (pinfunction "1_1") (pintype "passive"))
      (node (ref "FB29") (pin "2") (pinfunction "2_2") (pintype "passive"))
      (node (ref "FB30") (pin "2") (pinfunction "2_2") (pintype "passive"))
      (node (ref "IC48") (pin "7") (pinfunction "VCC_7") (pintype "power_in"))
      (node (ref "IC53") (pin "1") (pinfunction "VDD_1") (pintype "power_in"))
      (node (ref "IC82") (pin "1") (pinfunction "VDD_1") (pintype "power_in"))
      (node (ref "L13") (pin "2") (pinfunction "2_2") (pintype "passive"))
      (node (ref "R219") (pin "1") (pinfunction "1_1") (pintype "passive"))
      (node (ref "R317") (pin "2") (pinfunction "2_2") (pintype "passive"))
    )
    (net (code "64") (name "PVADJ2") (class "Default")
      (node (ref "C403") (pin "2") (pinfunction "2_2") (pintype "passive"))
      (node (ref "C408") (pin "2") (pinfunction "2_2") (pintype "passive"))
      (node (ref "IC41") (pin "1") (pinfunction "VCCA_1") (pintype "power_in"))
      (node (ref "IC41") (pin "2") (pinfunction "DIR_2") (pintype "input"))
      (node (ref "IC42") (pin "2") (pinfunction "VREF1_2") (pintype "input"))
      (node (ref "R454") (pin "1") (pinfunction "1_1") (pintype "passive"))
      (node (ref "R455") (pin "1") (pinfunction "1_1") (pintype "passive"))
    )
    (net (code "65") (name "unconnected-(IC38-NC-Pad6)") (class "Default")
      (node (ref "IC38") (pin "6") (pinfunction "NC_6") (pintype "passive"))
    )
    (net (code "66") (name "unconnected-(IC41-A8-Pad10)") (class "Default")
      (node (ref "IC41") (pin "10") (pinfunction "A8_10") (pintype "bidirectional"))
    )
    (net (code "67") (name "unconnected-(IC41-B8-Pad14)") (class "Default")
      (node (ref "IC41") (pin "14") (pinfunction "B8_14") (pintype "bidirectional"))
    )
    (net (code "68") (name "unconnected-(OSC2-CLK--Pad5)") (class "Default")
      (node (ref "OSC2") (pin "5") (pinfunction "CLK-_5") (pintype "output"))
    )
    (net (code "69") (name "unconnected-(OSC3-NC-Pad2)") (class "Default")
      (node (ref "OSC3") (pin "2") (pinfunction "NC_2") (pintype "passive"))
    )
  )
)
